# Steering_Wheel_Interface_Schmitt_Inverte.net
KiCad netlist of a schematic drawn in Altium Designer
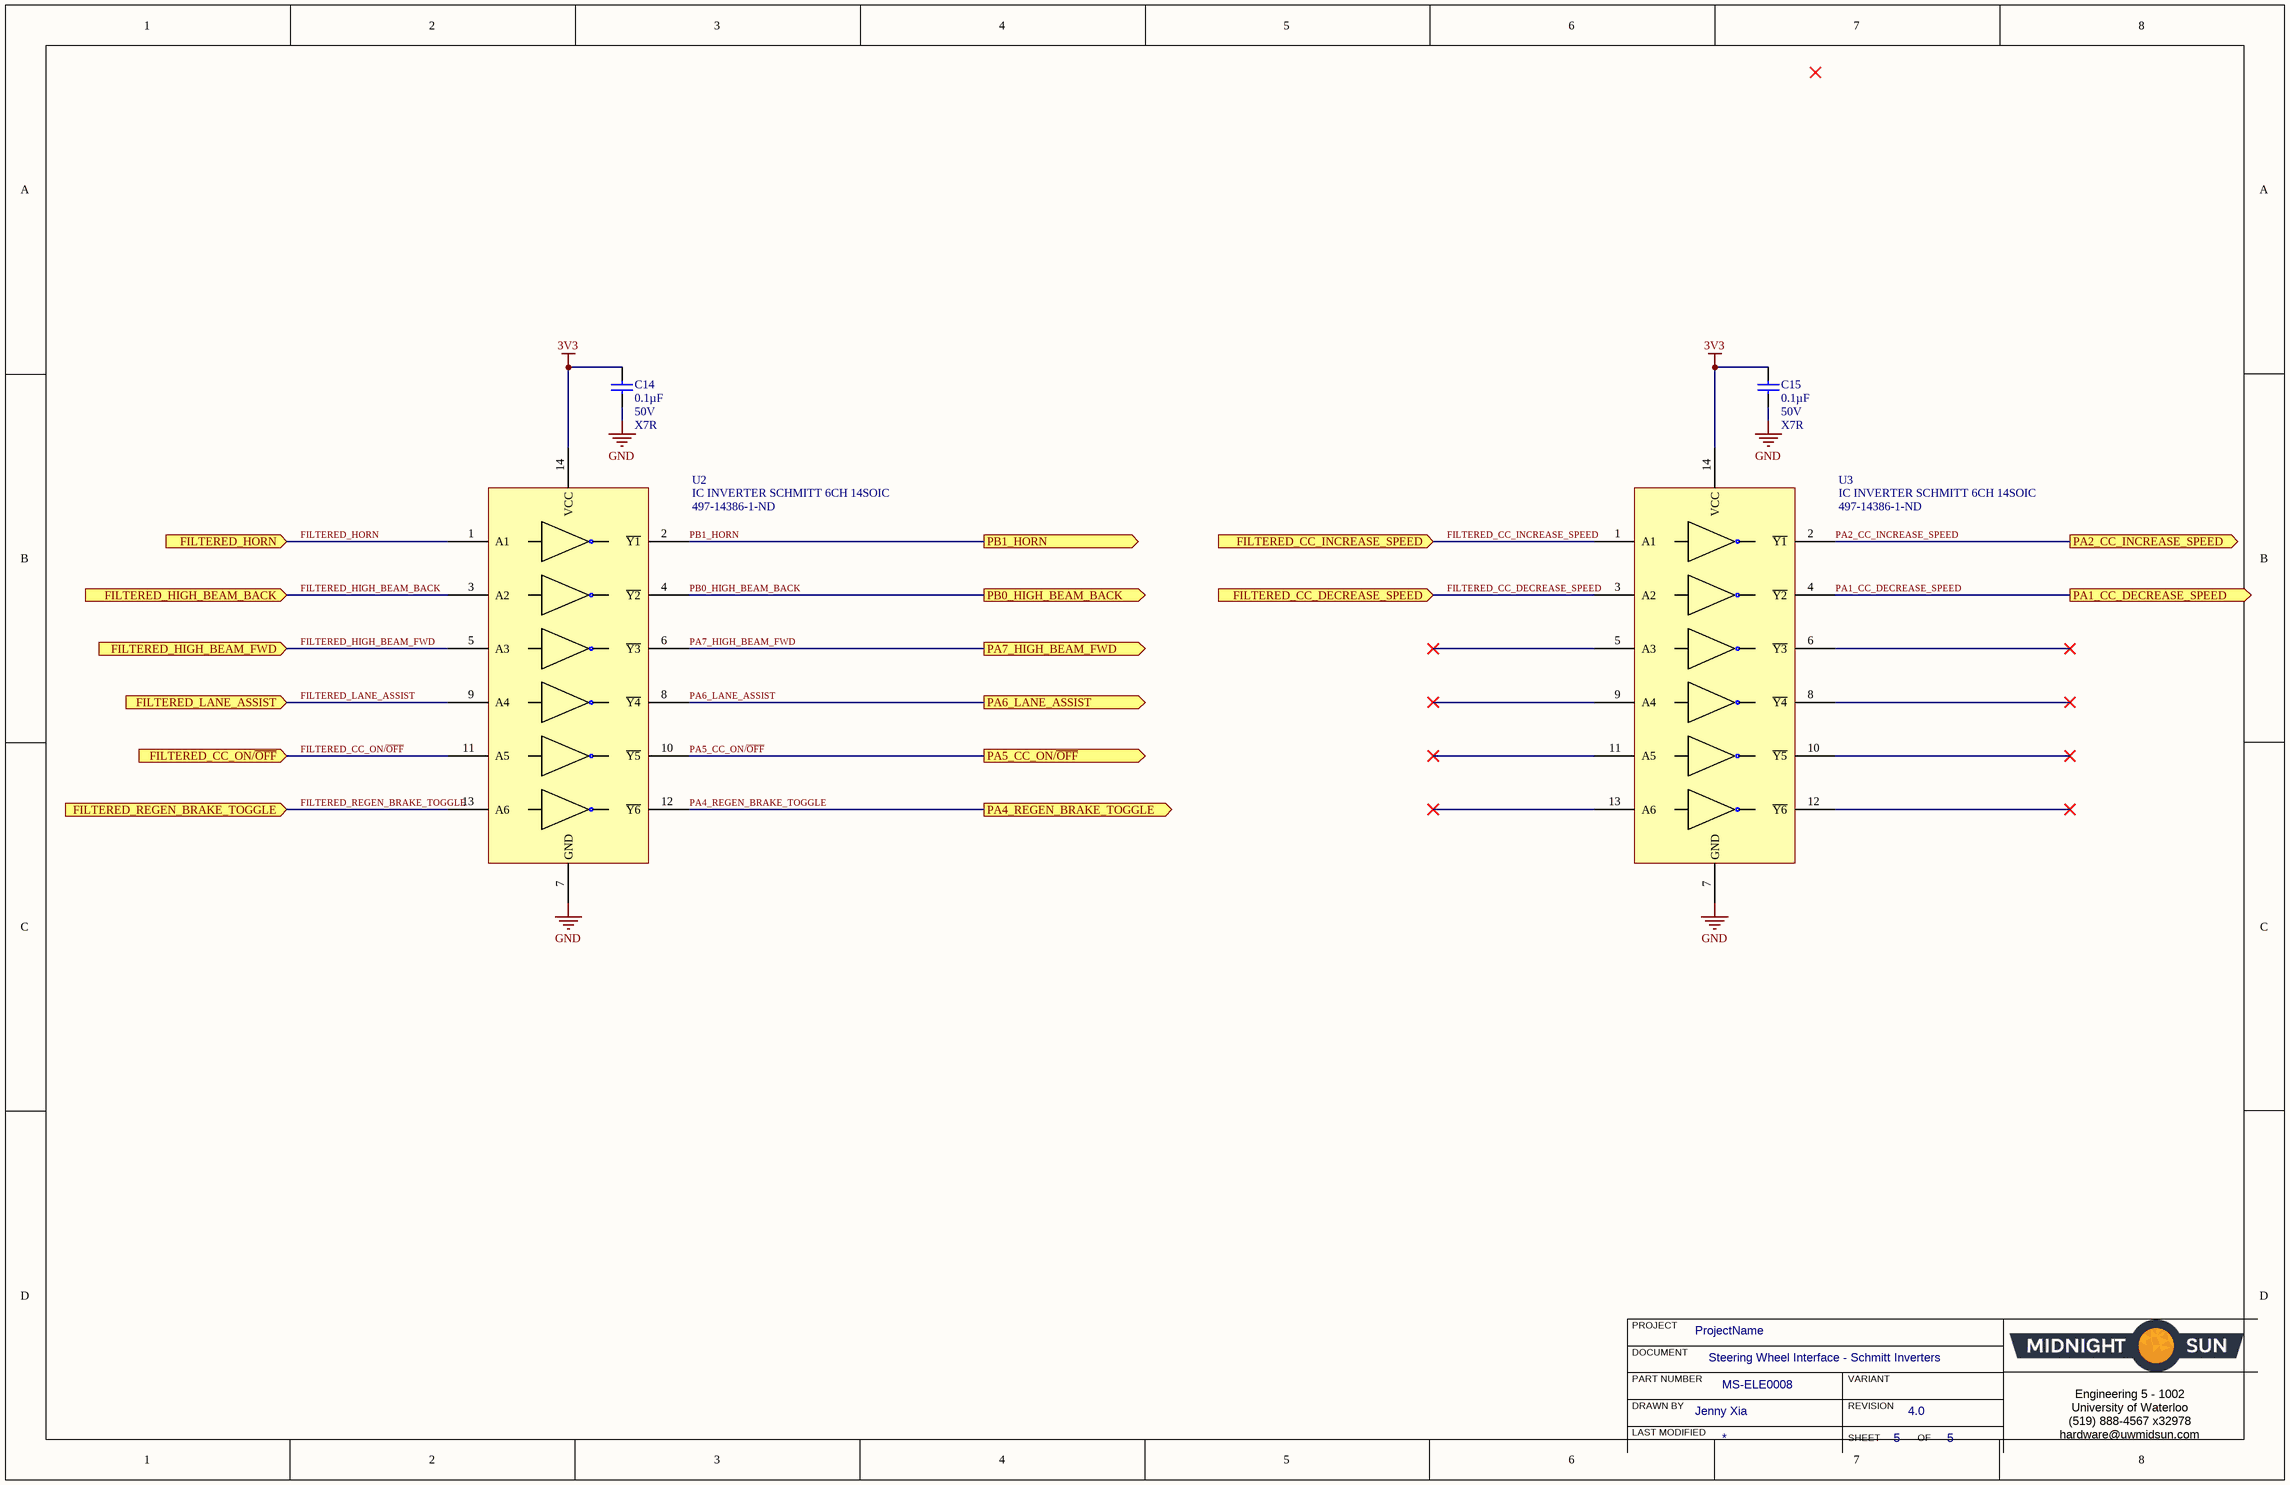
[diagram p0: Steering Wheel Interface Schmitt Inverters.SchDoc]

(export (version "E")
  (design (tool "Eeschema 10.0.6"))
  (components
    (comp (ref "C14")
      (value "CAP CER 0.1UF 50V 10% X7R 0603")
      (footprint "CAP, 0603")
      (description "0.10µF ±10% 50V Ceramic Capacitor X7R 0603 (1608 Metric)")
      (fields
        (field (name "TOLERANCE") "±10%")
        (field (name "CAPACITANCE") "0.1µF")
        (field (name "VOLTAGE") "50V")
        (field (name "TEMPERATURE COEFFICIENT") "X7R")
      )
      (libsource (lib "Schematic Diagrams") (part "CAP CER 0.1UF 50V 10% X7R 0603"))
    )
    (comp (ref "C15")
      (value "CAP CER 0.1UF 50V 10% X7R 0603")
      (footprint "CAP, 0603")
      (description "0.10µF ±10% 50V Ceramic Capacitor X7R 0603 (1608 Metric)")
      (fields
        (field (name "TOLERANCE") "±10%")
        (field (name "CAPACITANCE") "0.1µF")
        (field (name "VOLTAGE") "50V")
        (field (name "TEMPERATURE COEFFICIENT") "X7R")
      )
      (libsource (lib "Schematic Diagrams") (part "CAP CER 0.1UF 50V 10% X7R 0603"))
    )
    (comp (ref "U2")
      (value "IC INVERTER SCHMITT 6CH 14SOIC")
      (footprint "IC INVERTER SCHMITT 6CH 14TSSOP")
      (description "Inverter IC 6 Channel Schmitt Trigger 14-SOIC")
      (fields
        (field (name "MANUFACTURER") "STMicroelectronics")
        (field (name "MANUFACTURER PART NUMBER") "M74HC14YRM13TR")
        (field (name "SUPPLIER PART NUMBER 1") "497-14386-1-ND")
      )
      (libsource (lib "Schematic Diagrams") (part "IC INVERTER SCHMITT 6CH 14TSSOP"))
    )
    (comp (ref "U3")
      (value "IC INVERTER SCHMITT 6CH 14SOIC")
      (footprint "IC INVERTER SCHMITT 6CH 14TSSOP")
      (description "Inverter IC 6 Channel Schmitt Trigger 14-SOIC")
      (fields
        (field (name "MANUFACTURER") "STMicroelectronics")
        (field (name "MANUFACTURER PART NUMBER") "M74HC14YRM13TR")
        (field (name "SUPPLIER PART NUMBER 1") "497-14386-1-ND")
      )
      (libsource (lib "Schematic Diagrams") (part "IC INVERTER SCHMITT 6CH 14TSSOP"))
    )
  )
  (nets
    (net (code "1") (name "/FILTERED_CC_DECREASE_SPEED") (class "Default")
      (node (ref "U3") (pin "3") (pinfunction "A2_3") (pintype "passive"))
    )
    (net (code "2") (name "/FILTERED_CC_INCREASE_SPEED") (class "Default")
      (node (ref "U3") (pin "1") (pinfunction "A1_1") (pintype "passive"))
    )
    (net (code "3") (name "/FILTERED_CC_ON{slash}~{OFF}") (class "Default")
      (node (ref "U2") (pin "11") (pinfunction "A5_11") (pintype "passive"))
    )
    (net (code "4") (name "/FILTERED_HIGH_BEAM_BACK") (class "Default")
      (node (ref "U2") (pin "3") (pinfunction "A2_3") (pintype "passive"))
    )
    (net (code "5") (name "/FILTERED_HIGH_BEAM_FWD") (class "Default")
      (node (ref "U2") (pin "5") (pinfunction "A3_5") (pintype "passive"))
    )
    (net (code "6") (name "/FILTERED_HORN") (class "Default")
      (node (ref "U2") (pin "1") (pinfunction "A1_1") (pintype "passive"))
    )
    (net (code "7") (name "/FILTERED_LANE_ASSIST") (class "Default")
      (node (ref "U2") (pin "9") (pinfunction "A4_9") (pintype "passive"))
    )
    (net (code "8") (name "/FILTERED_REGEN_BRAKE_TOGGLE") (class "Default")
      (node (ref "U2") (pin "13") (pinfunction "A6_13") (pintype "passive"))
    )
    (net (code "9") (name "/PA1_CC_DECREASE_SPEED") (class "Default")
      (node (ref "U3") (pin "4") (pinfunction "~{Y2}_4") (pintype "passive"))
    )
    (net (code "10") (name "/PA2_CC_INCREASE_SPEED") (class "Default")
      (node (ref "U3") (pin "2") (pinfunction "~{Y1}_2") (pintype "passive"))
    )
    (net (code "11") (name "/PA4_REGEN_BRAKE_TOGGLE") (class "Default")
      (node (ref "U2") (pin "12") (pinfunction "~{Y6}_12") (pintype "passive"))
    )
    (net (code "12") (name "/PA5_CC_ON{slash}~{OFF}") (class "Default")
      (node (ref "U2") (pin "10") (pinfunction "~{Y5}_10") (pintype "passive"))
    )
    (net (code "13") (name "/PA6_LANE_ASSIST") (class "Default")
      (node (ref "U2") (pin "8") (pinfunction "~{Y4}_8") (pintype "passive"))
    )
    (net (code "14") (name "/PA7_HIGH_BEAM_FWD") (class "Default")
      (node (ref "U2") (pin "6") (pinfunction "~{Y3}_6") (pintype "passive"))
    )
    (net (code "15") (name "/PB0_HIGH_BEAM_BACK") (class "Default")
      (node (ref "U2") (pin "4") (pinfunction "~{Y2}_4") (pintype "passive"))
    )
    (net (code "16") (name "/PB1_HORN") (class "Default")
      (node (ref "U2") (pin "2") (pinfunction "~{Y1}_2") (pintype "passive"))
    )
    (net (code "17") (name "3V3") (class "Default")
      (node (ref "C14") (pin "1") (pinfunction "1_1") (pintype "passive"))
      (node (ref "C15") (pin "1") (pinfunction "1_1") (pintype "passive"))
      (node (ref "U2") (pin "14") (pinfunction "VCC_14") (pintype "passive"))
      (node (ref "U3") (pin "14") (pinfunction "VCC_14") (pintype "passive"))
    )
    (net (code "18") (name "GND") (class "Default")
      (node (ref "C14") (pin "2") (pinfunction "2_2") (pintype "passive"))
      (node (ref "C15") (pin "2") (pinfunction "2_2") (pintype "passive"))
      (node (ref "U2") (pin "7") (pinfunction "GND_7") (pintype "passive"))
      (node (ref "U3") (pin "7") (pinfunction "GND_7") (pintype "passive"))
    )
    (net (code "19") (name "unconnected-(U3-A3-Pad5)") (class "Default")
      (node (ref "U3") (pin "5") (pinfunction "A3_5") (pintype "passive+no_connect"))
    )
    (net (code "20") (name "unconnected-(U3-A4-Pad9)") (class "Default")
      (node (ref "U3") (pin "9") (pinfunction "A4_9") (pintype "passive+no_connect"))
    )
    (net (code "21") (name "unconnected-(U3-A5-Pad11)") (class "Default")
      (node (ref "U3") (pin "11") (pinfunction "A5_11") (pintype "passive+no_connect"))
    )
    (net (code "22") (name "unconnected-(U3-A6-Pad13)") (class "Default")
      (node (ref "U3") (pin "13") (pinfunction "A6_13") (pintype "passive+no_connect"))
    )
    (net (code "23") (name "unconnected-(U3-~{Y3}-Pad6)") (class "Default")
      (node (ref "U3") (pin "6") (pinfunction "~{Y3}_6") (pintype "passive+no_connect"))
    )
    (net (code "24") (name "unconnected-(U3-~{Y4}-Pad8)") (class "Default")
      (node (ref "U3") (pin "8") (pinfunction "~{Y4}_8") (pintype "passive+no_connect"))
    )
    (net (code "25") (name "unconnected-(U3-~{Y5}-Pad10)") (class "Default")
      (node (ref "U3") (pin "10") (pinfunction "~{Y5}_10") (pintype "passive+no_connect"))
    )
    (net (code "26") (name "unconnected-(U3-~{Y6}-Pad12)") (class "Default")
      (node (ref "U3") (pin "12") (pinfunction "~{Y6}_12") (pintype "passive+no_connect"))
    )
  )
)
